# BME280_I2C.net
KiCad netlist of a schematic drawn in Altium Designer
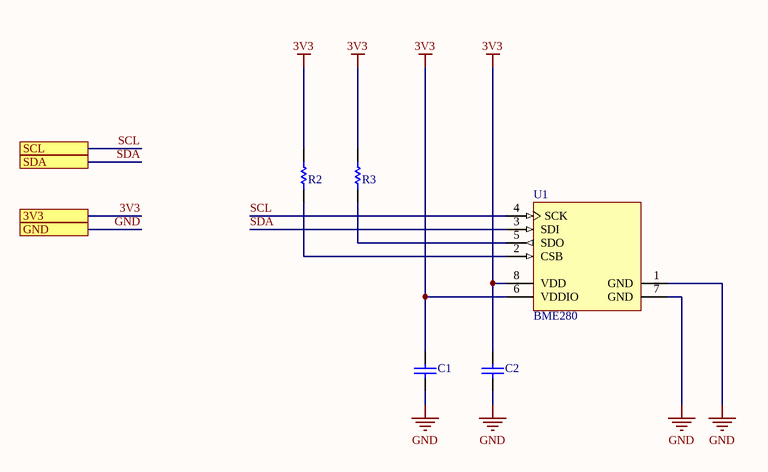
[diagram p0: BME280_I2C.SchDoc]

(export (version "E")
  (design (tool "Eeschema 10.0.6"))
  (components
    (comp (ref "C1")
      (value "C0805C104J5RAC7800")
      (footprint "CAPC2013X145X50NL20T25")
      (description "0.1µF ±5% 50V Ceramic Capacitor X7R 0805 (2012 Metric)")
      (fields (field (name "MANUFACTURER") "Kemet"))
      (libsource (lib "Altium Content Vault") (part "CAP"))
    )
    (comp (ref "C2")
      (value "C0805C104J5RAC7800")
      (footprint "CAPC2013X145X50NL20T25")
      (description "0.1µF ±5% 50V Ceramic Capacitor X7R 0805 (2012 Metric)")
      (fields (field (name "MANUFACTURER") "Kemet"))
      (libsource (lib "Altium Content Vault") (part "CAP"))
    )
    (comp (ref "R2")
      (value "RC0805JR-074K7L")
      (footprint "RESC2013X60X30NL20T20")
      (description "4.7 kOhms ±5% 0.125W, 1/8W Chip Resistor 0805 (2012 Metric) Moisture Resistant Thick Film")
      (fields (field (name "MANUFACTURER") "Yageo"))
      (libsource (lib "LIB_FIT") (part "RC0805JR-074K7L"))
    )
    (comp (ref "R3")
      (value "RC0805JR-074K7L")
      (footprint "RESC2013X60X30NL20T20")
      (description "4.7 kOhms ±5% 0.125W, 1/8W Chip Resistor 0805 (2012 Metric) Moisture Resistant Thick Film")
      (fields (field (name "MANUFACTURER") "Yageo"))
      (libsource (lib "LIB_FIT") (part "RC0805JR-074K7L"))
    )
    (comp (ref "U1")
      (value "BME280")
      (footprint "BOSC-BME280-8_V")
      (fields (field (name "MANUFACTURER") "Bosch Sensortec"))
      (libsource (lib "Altium Content Vault") (part "BOSC-BME280-8"))
    )
  )
  (nets
    (net (code "1") (name "/SCL") (class "Default")
      (node (ref "U1") (pin "4") (pinfunction "SCK_4") (pintype "input"))
    )
    (net (code "2") (name "/SDA") (class "Default")
      (node (ref "U1") (pin "3") (pinfunction "SDI_3") (pintype "input"))
    )
    (net (code "3") (name "3V3") (class "Default")
      (node (ref "C1") (pin "2") (pinfunction "2_2") (pintype "passive"))
      (node (ref "C2") (pin "2") (pinfunction "2_2") (pintype "passive"))
      (node (ref "R2") (pin "2") (pinfunction "2_2") (pintype "passive"))
      (node (ref "R3") (pin "2") (pinfunction "2_2") (pintype "passive"))
      (node (ref "U1") (pin "6") (pinfunction "VDDIO_6") (pintype "power_in"))
      (node (ref "U1") (pin "8") (pinfunction "VDD_8") (pintype "power_in"))
    )
    (net (code "4") (name "GND") (class "Default")
      (node (ref "C1") (pin "1") (pinfunction "1_1") (pintype "passive"))
      (node (ref "C2") (pin "1") (pinfunction "1_1") (pintype "passive"))
      (node (ref "U1") (pin "1") (pinfunction "GND_1") (pintype "power_in"))
      (node (ref "U1") (pin "7") (pinfunction "GND_7") (pintype "power_in"))
    )
    (net (code "5") (name "Net-(U1-CSB)") (class "Default")
      (node (ref "R2") (pin "1") (pinfunction "1_1") (pintype "passive"))
      (node (ref "U1") (pin "2") (pinfunction "CSB_2") (pintype "input"))
    )
    (net (code "6") (name "Net-(U1-SDO)") (class "Default")
      (node (ref "R3") (pin "1") (pinfunction "1_1") (pintype "passive"))
      (node (ref "U1") (pin "5") (pinfunction "SDO_5") (pintype "output"))
    )
  )
)
